# reza-connectboard.net
KiCad netlist of a schematic drawn in EAGLE
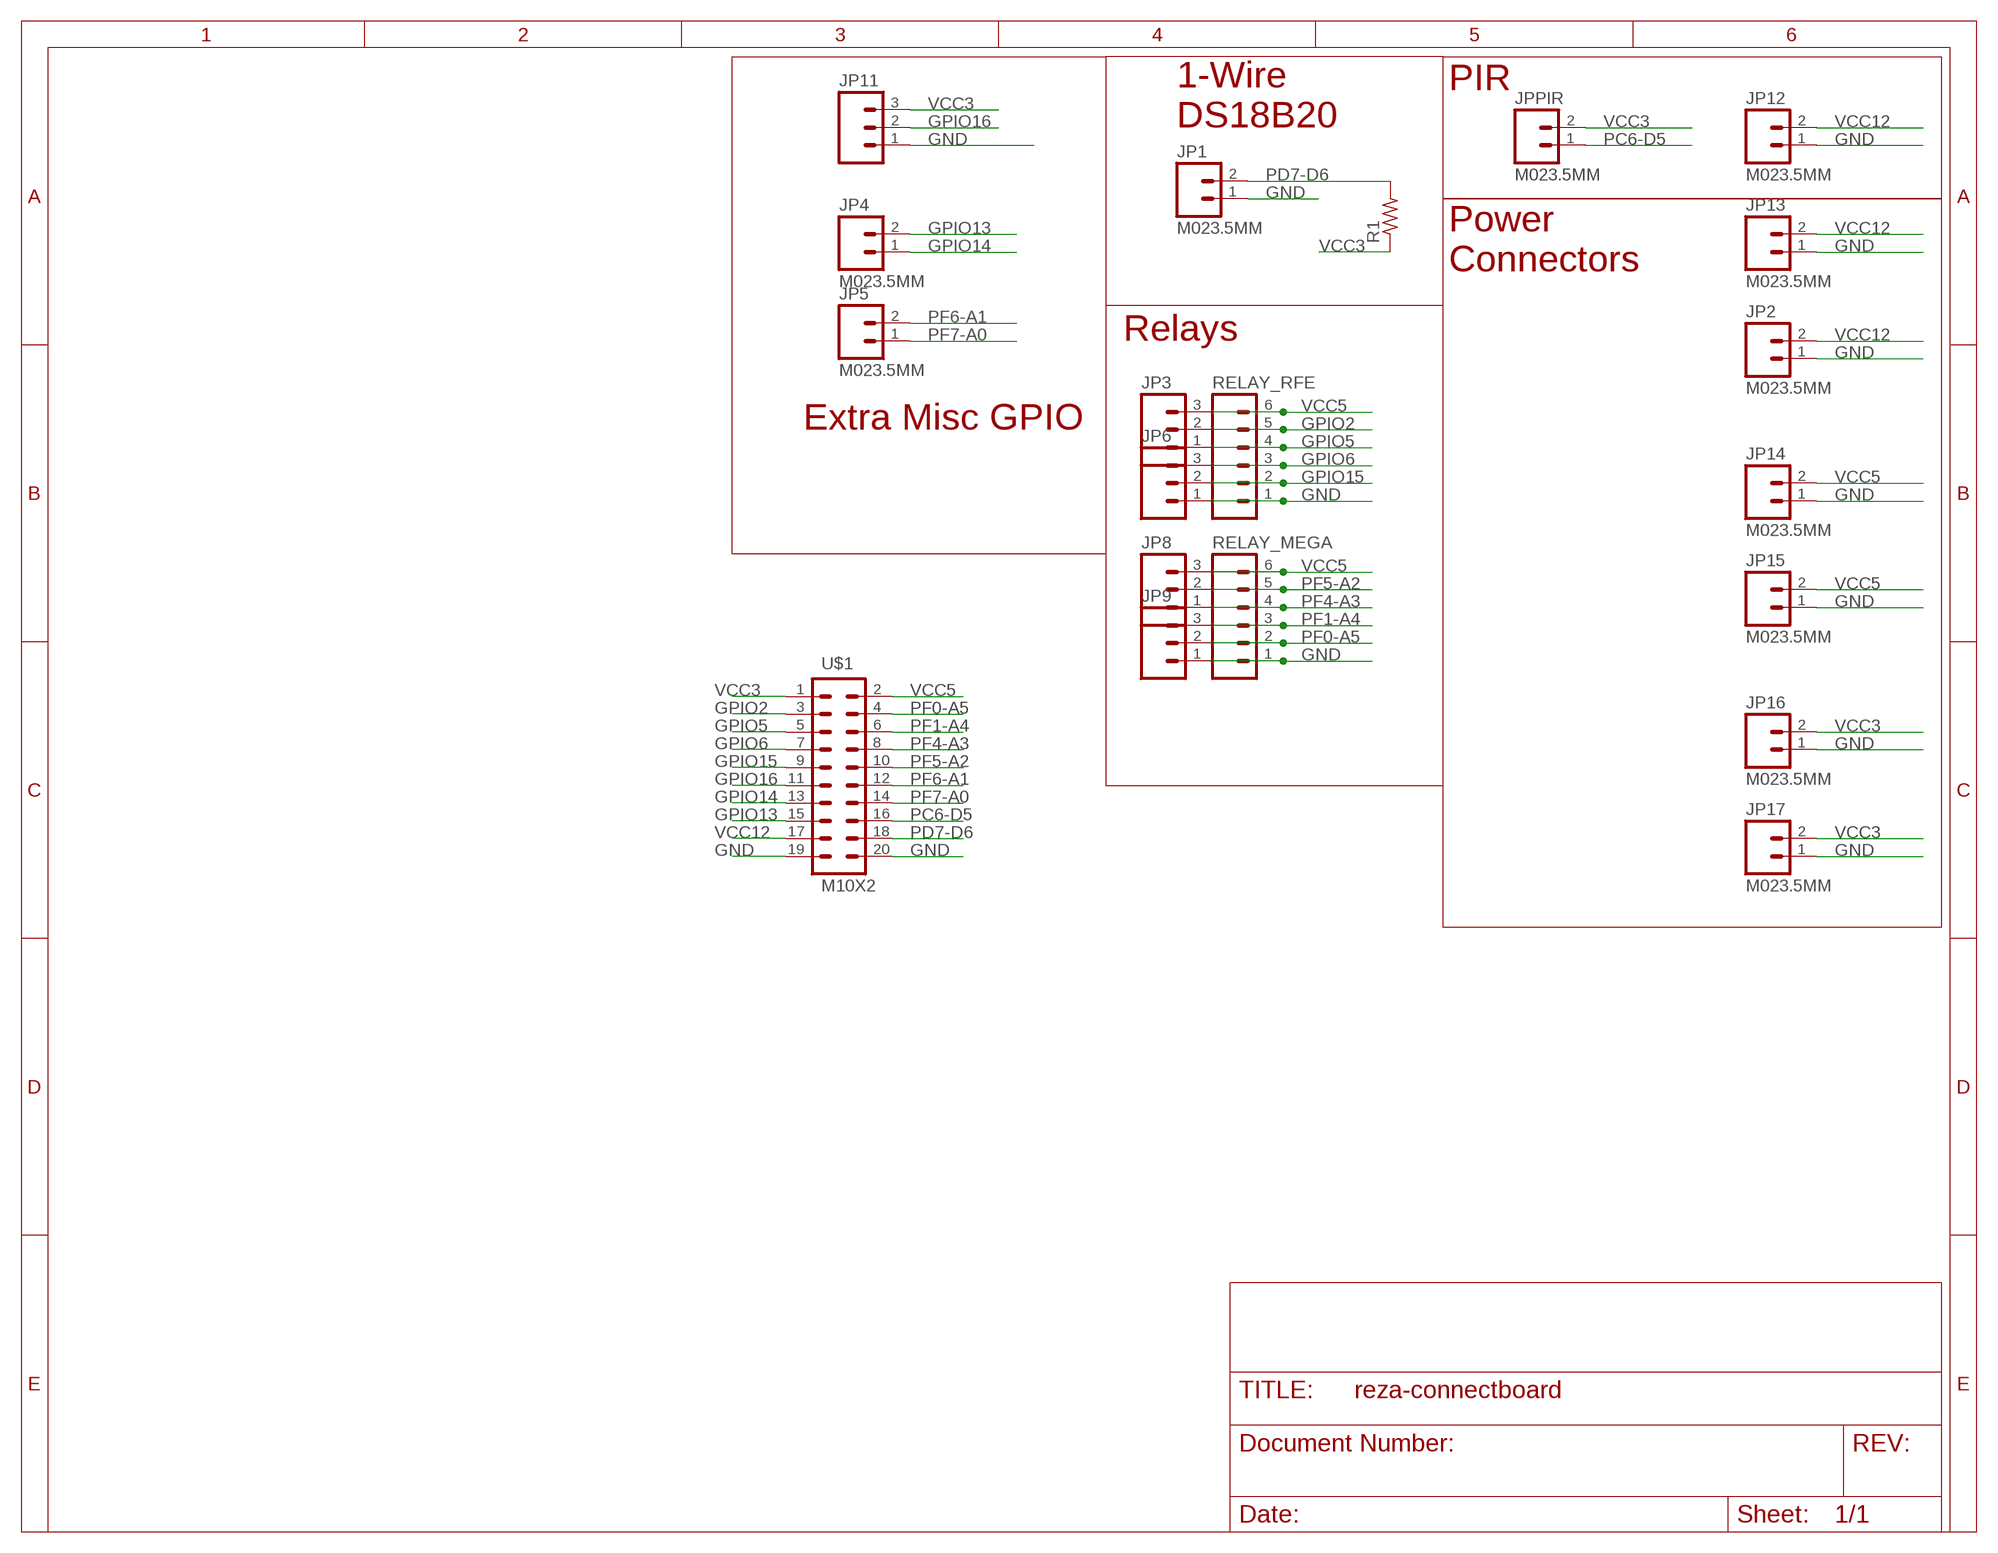
[diagram p0: schematic, sheet 1]

(export (version "E")
  (design (tool "Eeschema 10.0.6"))
  (components
    (comp (ref "JP1")
      (value "M023.5MM")
      (footprint "eagle-import:SCREWTERMINAL-3.5MM-2")
      (libsource (lib "eagle-import") (part "M023.5MM"))
    )
    (comp (ref "JP2")
      (value "M023.5MM")
      (footprint "eagle-import:SCREWTERMINAL-3.5MM-2")
      (libsource (lib "eagle-import") (part "M023.5MM"))
    )
    (comp (ref "JP3")
      (value "M03SCREW")
      (footprint "eagle-import:SCREWTERMINAL-3.5MM-3")
      (libsource (lib "eagle-import") (part "M03SCREW"))
    )
    (comp (ref "JP4")
      (value "M023.5MM")
      (footprint "eagle-import:SCREWTERMINAL-3.5MM-2")
      (libsource (lib "eagle-import") (part "M023.5MM"))
    )
    (comp (ref "JP5")
      (value "M023.5MM")
      (footprint "eagle-import:SCREWTERMINAL-3.5MM-2")
      (libsource (lib "eagle-import") (part "M023.5MM"))
    )
    (comp (ref "JP6")
      (value "M03SCREW")
      (footprint "eagle-import:SCREWTERMINAL-3.5MM-3")
      (libsource (lib "eagle-import") (part "M03SCREW"))
    )
    (comp (ref "JP8")
      (value "M03SCREW")
      (footprint "eagle-import:SCREWTERMINAL-3.5MM-3")
      (libsource (lib "eagle-import") (part "M03SCREW"))
    )
    (comp (ref "JP9")
      (value "M03SCREW")
      (footprint "eagle-import:SCREWTERMINAL-3.5MM-3")
      (libsource (lib "eagle-import") (part "M03SCREW"))
    )
    (comp (ref "JP11")
      (value "M03SCREW")
      (footprint "eagle-import:SCREWTERMINAL-3.5MM-3")
      (libsource (lib "eagle-import") (part "M03SCREW"))
    )
    (comp (ref "JP12")
      (value "M023.5MM")
      (footprint "eagle-import:SCREWTERMINAL-3.5MM-2")
      (libsource (lib "eagle-import") (part "M023.5MM"))
    )
    (comp (ref "JP13")
      (value "M023.5MM")
      (footprint "eagle-import:SCREWTERMINAL-3.5MM-2")
      (libsource (lib "eagle-import") (part "M023.5MM"))
    )
    (comp (ref "JP14")
      (value "M023.5MM")
      (footprint "eagle-import:SCREWTERMINAL-3.5MM-2")
      (libsource (lib "eagle-import") (part "M023.5MM"))
    )
    (comp (ref "JP15")
      (value "M023.5MM")
      (footprint "eagle-import:SCREWTERMINAL-3.5MM-2")
      (libsource (lib "eagle-import") (part "M023.5MM"))
    )
    (comp (ref "JP16")
      (value "M023.5MM")
      (footprint "eagle-import:SCREWTERMINAL-3.5MM-2")
      (libsource (lib "eagle-import") (part "M023.5MM"))
    )
    (comp (ref "JP17")
      (value "M023.5MM")
      (footprint "eagle-import:SCREWTERMINAL-3.5MM-2")
      (libsource (lib "eagle-import") (part "M023.5MM"))
    )
    (comp (ref "JPPIR")
      (value "M023.5MM")
      (footprint "eagle-import:SCREWTERMINAL-3.5MM-2")
      (libsource (lib "eagle-import") (part "M023.5MM"))
    )
    (comp (ref "R1")
      (value "R-US_FLIPFLOP")
      (footprint "eagle-import:0805-THM")
      (libsource (lib "eagle-import") (part "R-US_FLIPFLOP"))
    )
    (comp (ref "RELAY_MEGA")
      (value "M06SIP")
      (footprint "eagle-import:1X06")
      (libsource (lib "eagle-import") (part "M06SIP"))
    )
    (comp (ref "RELAY_RFE")
      (value "M06SIP")
      (footprint "eagle-import:1X06")
      (libsource (lib "eagle-import") (part "M06SIP"))
    )
    (comp (ref "U$1")
      (value "M10X2")
      (footprint "eagle-import:2X10")
      (libsource (lib "eagle-import") (part "M10X2"))
    )
  )
  (nets
    (net (code "1") (name "/GND") (class "Default")
      (node (ref "JP1") (pin "1") (pinfunction "1_1") (pintype "passive"))
      (node (ref "JP11") (pin "1") (pinfunction "1_1") (pintype "passive"))
      (node (ref "JP12") (pin "1") (pinfunction "1_1") (pintype "passive"))
      (node (ref "JP13") (pin "1") (pinfunction "1_1") (pintype "passive"))
      (node (ref "JP14") (pin "1") (pinfunction "1_1") (pintype "passive"))
      (node (ref "JP15") (pin "1") (pinfunction "1_1") (pintype "passive"))
      (node (ref "JP16") (pin "1") (pinfunction "1_1") (pintype "passive"))
      (node (ref "JP17") (pin "1") (pinfunction "1_1") (pintype "passive"))
      (node (ref "JP2") (pin "1") (pinfunction "1_1") (pintype "passive"))
      (node (ref "JP6") (pin "1") (pinfunction "1_1") (pintype "passive"))
      (node (ref "JP9") (pin "1") (pinfunction "1_1") (pintype "passive"))
      (node (ref "RELAY_MEGA") (pin "1") (pinfunction "1_1") (pintype "passive"))
      (node (ref "RELAY_RFE") (pin "1") (pinfunction "1_1") (pintype "passive"))
      (node (ref "U$1") (pin "19") (pinfunction "19_19") (pintype "passive"))
      (node (ref "U$1") (pin "20") (pinfunction "20_20") (pintype "passive"))
    )
    (net (code "2") (name "/GPIO2") (class "Default")
      (node (ref "JP3") (pin "2") (pinfunction "2_2") (pintype "passive"))
      (node (ref "RELAY_RFE") (pin "5") (pinfunction "5_5") (pintype "passive"))
      (node (ref "U$1") (pin "3") (pinfunction "3_3") (pintype "passive"))
    )
    (net (code "3") (name "/GPIO5") (class "Default")
      (node (ref "JP3") (pin "1") (pinfunction "1_1") (pintype "passive"))
      (node (ref "RELAY_RFE") (pin "4") (pinfunction "4_4") (pintype "passive"))
      (node (ref "U$1") (pin "5") (pinfunction "5_5") (pintype "passive"))
    )
    (net (code "4") (name "/GPIO6") (class "Default")
      (node (ref "JP6") (pin "3") (pinfunction "3_3") (pintype "passive"))
      (node (ref "RELAY_RFE") (pin "3") (pinfunction "3_3") (pintype "passive"))
      (node (ref "U$1") (pin "7") (pinfunction "7_7") (pintype "passive"))
    )
    (net (code "5") (name "/GPIO13") (class "Default")
      (node (ref "JP4") (pin "2") (pinfunction "2_2") (pintype "passive"))
      (node (ref "U$1") (pin "15") (pinfunction "15_15") (pintype "passive"))
    )
    (net (code "6") (name "/GPIO14") (class "Default")
      (node (ref "JP4") (pin "1") (pinfunction "1_1") (pintype "passive"))
      (node (ref "U$1") (pin "13") (pinfunction "13_13") (pintype "passive"))
    )
    (net (code "7") (name "/GPIO15") (class "Default")
      (node (ref "JP6") (pin "2") (pinfunction "2_2") (pintype "passive"))
      (node (ref "RELAY_RFE") (pin "2") (pinfunction "2_2") (pintype "passive"))
      (node (ref "U$1") (pin "9") (pinfunction "9_9") (pintype "passive"))
    )
    (net (code "8") (name "/GPIO16") (class "Default")
      (node (ref "JP11") (pin "2") (pinfunction "2_2") (pintype "passive"))
      (node (ref "U$1") (pin "11") (pinfunction "11_11") (pintype "passive"))
    )
    (net (code "9") (name "/PC6-D5") (class "Default")
      (node (ref "JPPIR") (pin "1") (pinfunction "1_1") (pintype "passive"))
      (node (ref "U$1") (pin "16") (pinfunction "16_16") (pintype "passive"))
    )
    (net (code "10") (name "/PD7-D6") (class "Default")
      (node (ref "JP1") (pin "2") (pinfunction "2_2") (pintype "passive"))
      (node (ref "R1") (pin "2") (pinfunction "2_2") (pintype "passive"))
      (node (ref "U$1") (pin "18") (pinfunction "18_18") (pintype "passive"))
    )
    (net (code "11") (name "/PF0-A5") (class "Default")
      (node (ref "JP9") (pin "2") (pinfunction "2_2") (pintype "passive"))
      (node (ref "RELAY_MEGA") (pin "2") (pinfunction "2_2") (pintype "passive"))
      (node (ref "U$1") (pin "4") (pinfunction "4_4") (pintype "passive"))
    )
    (net (code "12") (name "/PF1-A4") (class "Default")
      (node (ref "JP9") (pin "3") (pinfunction "3_3") (pintype "passive"))
      (node (ref "RELAY_MEGA") (pin "3") (pinfunction "3_3") (pintype "passive"))
      (node (ref "U$1") (pin "6") (pinfunction "6_6") (pintype "passive"))
    )
    (net (code "13") (name "/PF4-A3") (class "Default")
      (node (ref "JP8") (pin "1") (pinfunction "1_1") (pintype "passive"))
      (node (ref "RELAY_MEGA") (pin "4") (pinfunction "4_4") (pintype "passive"))
      (node (ref "U$1") (pin "8") (pinfunction "8_8") (pintype "passive"))
    )
    (net (code "14") (name "/PF5-A2") (class "Default")
      (node (ref "JP8") (pin "2") (pinfunction "2_2") (pintype "passive"))
      (node (ref "RELAY_MEGA") (pin "5") (pinfunction "5_5") (pintype "passive"))
      (node (ref "U$1") (pin "10") (pinfunction "10_10") (pintype "passive"))
    )
    (net (code "15") (name "/PF6-A1") (class "Default")
      (node (ref "JP5") (pin "2") (pinfunction "2_2") (pintype "passive"))
      (node (ref "U$1") (pin "12") (pinfunction "12_12") (pintype "passive"))
    )
    (net (code "16") (name "/PF7-A0") (class "Default")
      (node (ref "JP5") (pin "1") (pinfunction "1_1") (pintype "passive"))
      (node (ref "U$1") (pin "14") (pinfunction "14_14") (pintype "passive"))
    )
    (net (code "17") (name "/VCC3") (class "Default")
      (node (ref "JP11") (pin "3") (pinfunction "3_3") (pintype "passive"))
      (node (ref "JP16") (pin "2") (pinfunction "2_2") (pintype "passive"))
      (node (ref "JP17") (pin "2") (pinfunction "2_2") (pintype "passive"))
      (node (ref "JPPIR") (pin "2") (pinfunction "2_2") (pintype "passive"))
      (node (ref "R1") (pin "1") (pinfunction "1_1") (pintype "passive"))
      (node (ref "U$1") (pin "1") (pinfunction "1_1") (pintype "passive"))
    )
    (net (code "18") (name "/VCC5") (class "Default")
      (node (ref "JP14") (pin "2") (pinfunction "2_2") (pintype "passive"))
      (node (ref "JP15") (pin "2") (pinfunction "2_2") (pintype "passive"))
      (node (ref "JP3") (pin "3") (pinfunction "3_3") (pintype "passive"))
      (node (ref "JP8") (pin "3") (pinfunction "3_3") (pintype "passive"))
      (node (ref "RELAY_MEGA") (pin "6") (pinfunction "6_6") (pintype "passive"))
      (node (ref "RELAY_RFE") (pin "6") (pinfunction "6_6") (pintype "passive"))
      (node (ref "U$1") (pin "2") (pinfunction "2_2") (pintype "passive"))
    )
    (net (code "19") (name "/VCC12") (class "Default")
      (node (ref "JP12") (pin "2") (pinfunction "2_2") (pintype "passive"))
      (node (ref "JP13") (pin "2") (pinfunction "2_2") (pintype "passive"))
      (node (ref "JP2") (pin "2") (pinfunction "2_2") (pintype "passive"))
      (node (ref "U$1") (pin "17") (pinfunction "17_17") (pintype "passive"))
    )
  )
)
